# Sensor_Arduino.net
KiCad netlist of a schematic drawn in EAGLE
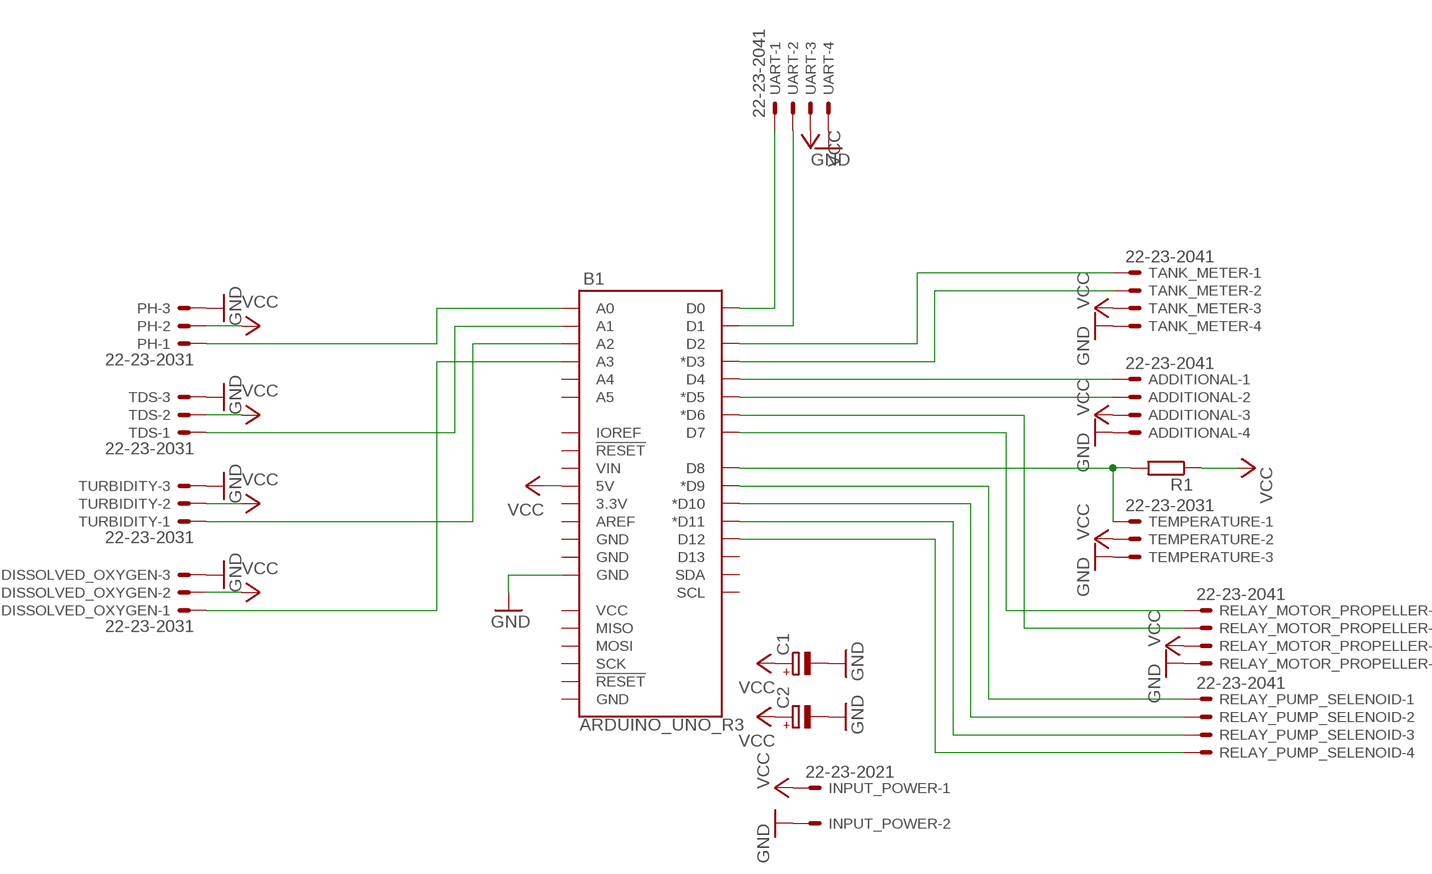
[diagram p0: schematic, sheet 1]

(export (version "E")
  (design (tool "Eeschema 10.0.6"))
  (components
    (comp (ref "ADDITIONAL")
      (value "22-23-2041")
      (footprint "eagle-import:22-23-2041")
      (fields (field (name "MF") "MOLEX"))
      (libsource (lib "eagle-import") (part "22-23-2041"))
    )
    (comp (ref "B1")
      (value "ARDUINO_UNO_R3")
      (footprint "eagle-import:ARDUINO_R3")
      (libsource (lib "eagle-import") (part "ARDUINO_UNO_R3"))
    )
    (comp (ref "C1")
      (value "CPOL-EUE5-10.5")
      (footprint "eagle-import:E5-10,5")
      (libsource (lib "eagle-import") (part "CPOL-EUE5-10.5"))
    )
    (comp (ref "C2")
      (value "CPOL-EUE5-6")
      (footprint "eagle-import:E5-6")
      (libsource (lib "eagle-import") (part "CPOL-EUE5-6"))
    )
    (comp (ref "DISSOLVED_OXYGEN")
      (value "22-23-2031")
      (footprint "eagle-import:22-23-2031")
      (fields (field (name "MF") "MOLEX"))
      (libsource (lib "eagle-import") (part "22-23-2031"))
    )
    (comp (ref "INPUT_POWER")
      (value "22-23-2021")
      (footprint "eagle-import:22-23-2021")
      (fields (field (name "MF") "MOLEX"))
      (libsource (lib "eagle-import") (part "22-23-2021"))
    )
    (comp (ref "PH")
      (value "22-23-2031")
      (footprint "eagle-import:22-23-2031")
      (fields (field (name "MF") "MOLEX"))
      (libsource (lib "eagle-import") (part "22-23-2031"))
    )
    (comp (ref "R1")
      (value "R-EU_0207/12")
      (footprint "eagle-import:0207_12")
      (libsource (lib "eagle-import") (part "R-EU_0207/12"))
    )
    (comp (ref "RELAY_MOTOR_PROPELLER")
      (value "22-23-2041")
      (footprint "eagle-import:22-23-2041")
      (fields (field (name "MF") "MOLEX"))
      (libsource (lib "eagle-import") (part "22-23-2041"))
    )
    (comp (ref "RELAY_PUMP_SELENOID")
      (value "22-23-2041")
      (footprint "eagle-import:22-23-2041")
      (fields (field (name "MF") "MOLEX"))
      (libsource (lib "eagle-import") (part "22-23-2041"))
    )
    (comp (ref "TANK_METER")
      (value "22-23-2041")
      (footprint "eagle-import:22-23-2041")
      (fields (field (name "MF") "MOLEX"))
      (libsource (lib "eagle-import") (part "22-23-2041"))
    )
    (comp (ref "TDS")
      (value "22-23-2031")
      (footprint "eagle-import:22-23-2031")
      (fields (field (name "MF") "MOLEX"))
      (libsource (lib "eagle-import") (part "22-23-2031"))
    )
    (comp (ref "TEMPERATURE")
      (value "22-23-2031")
      (footprint "eagle-import:22-23-2031")
      (fields (field (name "MF") "MOLEX"))
      (libsource (lib "eagle-import") (part "22-23-2031"))
    )
    (comp (ref "TURBIDITY")
      (value "22-23-2031")
      (footprint "eagle-import:22-23-2031")
      (fields (field (name "MF") "MOLEX"))
      (libsource (lib "eagle-import") (part "22-23-2031"))
    )
    (comp (ref "UART")
      (value "22-23-2041")
      (footprint "eagle-import:22-23-2041")
      (fields (field (name "MF") "MOLEX"))
      (libsource (lib "eagle-import") (part "22-23-2041"))
    )
  )
  (nets
    (net (code "1") (name "GND") (class "Default")
      (node (ref "ADDITIONAL") (pin "4") (pinfunction "S_4") (pintype "passive"))
      (node (ref "B1") (pin "GND@2") (pinfunction "GND_GND@2") (pintype "bidirectional"))
      (node (ref "C1") (pin "-") (pinfunction "-_-") (pintype "passive"))
      (node (ref "C2") (pin "-") (pinfunction "-_-") (pintype "passive"))
      (node (ref "DISSOLVED_OXYGEN") (pin "3") (pinfunction "S_3") (pintype "passive"))
      (node (ref "INPUT_POWER") (pin "2") (pinfunction "S_2") (pintype "passive"))
      (node (ref "PH") (pin "3") (pinfunction "S_3") (pintype "passive"))
      (node (ref "RELAY_MOTOR_PROPELLER") (pin "4") (pinfunction "S_4") (pintype "passive"))
      (node (ref "TANK_METER") (pin "4") (pinfunction "S_4") (pintype "passive"))
      (node (ref "TDS") (pin "3") (pinfunction "S_3") (pintype "passive"))
      (node (ref "TEMPERATURE") (pin "3") (pinfunction "S_3") (pintype "passive"))
      (node (ref "TURBIDITY") (pin "3") (pinfunction "S_3") (pintype "passive"))
      (node (ref "UART") (pin "4") (pinfunction "S_4") (pintype "passive"))
    )
    (net (code "2") (name "Net-(ADDITIONALA-S)") (class "Default")
      (node (ref "ADDITIONAL") (pin "1") (pinfunction "S_1") (pintype "passive"))
      (node (ref "B1") (pin "D4") (pinfunction "D4_D4") (pintype "bidirectional"))
    )
    (net (code "3") (name "Net-(ADDITIONALB-S)") (class "Default")
      (node (ref "ADDITIONAL") (pin "2") (pinfunction "S_2") (pintype "passive"))
      (node (ref "B1") (pin "D5") (pinfunction "*D5_D5") (pintype "bidirectional"))
    )
    (net (code "4") (name "Net-(B1-*D3)") (class "Default")
      (node (ref "B1") (pin "D3") (pinfunction "*D3_D3") (pintype "bidirectional"))
      (node (ref "TANK_METER") (pin "2") (pinfunction "S_2") (pintype "passive"))
    )
    (net (code "5") (name "Net-(B1-*D6)") (class "Default")
      (node (ref "B1") (pin "D6") (pinfunction "*D6_D6") (pintype "bidirectional"))
      (node (ref "RELAY_MOTOR_PROPELLER") (pin "2") (pinfunction "S_2") (pintype "passive"))
    )
    (net (code "6") (name "Net-(B1-*D9)") (class "Default")
      (node (ref "B1") (pin "D9") (pinfunction "*D9_D9") (pintype "bidirectional"))
      (node (ref "RELAY_PUMP_SELENOID") (pin "1") (pinfunction "S_1") (pintype "passive"))
    )
    (net (code "7") (name "Net-(B1-*D10)") (class "Default")
      (node (ref "B1") (pin "D10") (pinfunction "*D10_D10") (pintype "bidirectional"))
      (node (ref "RELAY_PUMP_SELENOID") (pin "2") (pinfunction "S_2") (pintype "passive"))
    )
    (net (code "8") (name "Net-(B1-*D11)") (class "Default")
      (node (ref "B1") (pin "D11") (pinfunction "*D11_D11") (pintype "bidirectional"))
      (node (ref "RELAY_PUMP_SELENOID") (pin "3") (pinfunction "S_3") (pintype "passive"))
    )
    (net (code "9") (name "Net-(DISSOLVED_OXYGENA-S)") (class "Default")
      (node (ref "B1") (pin "A3") (pinfunction "A3_A3") (pintype "bidirectional"))
      (node (ref "DISSOLVED_OXYGEN") (pin "1") (pinfunction "S_1") (pintype "passive"))
    )
    (net (code "10") (name "Net-(PHA-S)") (class "Default")
      (node (ref "B1") (pin "A0") (pinfunction "A0_A0") (pintype "bidirectional"))
      (node (ref "PH") (pin "1") (pinfunction "S_1") (pintype "passive"))
    )
    (net (code "11") (name "Net-(RELAY_MOTOR_PROPELLERA-S)") (class "Default")
      (node (ref "B1") (pin "D7") (pinfunction "D7_D7") (pintype "bidirectional"))
      (node (ref "RELAY_MOTOR_PROPELLER") (pin "1") (pinfunction "S_1") (pintype "passive"))
    )
    (net (code "12") (name "Net-(RELAY_PUMP_SELENOIDD-S)") (class "Default")
      (node (ref "B1") (pin "D12") (pinfunction "D12_D12") (pintype "bidirectional"))
      (node (ref "RELAY_PUMP_SELENOID") (pin "4") (pinfunction "S_4") (pintype "passive"))
    )
    (net (code "13") (name "Net-(TANK_METERA-S)") (class "Default")
      (node (ref "B1") (pin "D2") (pinfunction "D2_D2") (pintype "bidirectional"))
      (node (ref "TANK_METER") (pin "1") (pinfunction "S_1") (pintype "passive"))
    )
    (net (code "14") (name "Net-(TDSA-S)") (class "Default")
      (node (ref "B1") (pin "A1") (pinfunction "A1_A1") (pintype "bidirectional"))
      (node (ref "TDS") (pin "1") (pinfunction "S_1") (pintype "passive"))
    )
    (net (code "15") (name "Net-(TEMPERATUREA-S)") (class "Default")
      (node (ref "B1") (pin "D8") (pinfunction "D8_D8") (pintype "bidirectional"))
      (node (ref "R1") (pin "2") (pinfunction "2_2") (pintype "passive"))
      (node (ref "TEMPERATURE") (pin "1") (pinfunction "S_1") (pintype "passive"))
    )
    (net (code "16") (name "Net-(TURBIDITYA-S)") (class "Default")
      (node (ref "B1") (pin "A2") (pinfunction "A2_A2") (pintype "bidirectional"))
      (node (ref "TURBIDITY") (pin "1") (pinfunction "S_1") (pintype "passive"))
    )
    (net (code "17") (name "Net-(UARTA-S)") (class "Default")
      (node (ref "B1") (pin "D0") (pinfunction "D0_D0") (pintype "bidirectional"))
      (node (ref "UART") (pin "1") (pinfunction "S_1") (pintype "passive"))
    )
    (net (code "18") (name "Net-(UARTB-S)") (class "Default")
      (node (ref "B1") (pin "D1") (pinfunction "D1_D1") (pintype "bidirectional"))
      (node (ref "UART") (pin "2") (pinfunction "S_2") (pintype "passive"))
    )
    (net (code "19") (name "VCC") (class "Default")
      (node (ref "ADDITIONAL") (pin "3") (pinfunction "S_3") (pintype "passive"))
      (node (ref "B1") (pin "5V") (pinfunction "5V_5V") (pintype "bidirectional"))
      (node (ref "C1") (pin "+") (pinfunction "+_+") (pintype "passive"))
      (node (ref "C2") (pin "+") (pinfunction "+_+") (pintype "passive"))
      (node (ref "DISSOLVED_OXYGEN") (pin "2") (pinfunction "S_2") (pintype "passive"))
      (node (ref "INPUT_POWER") (pin "1") (pinfunction "S_1") (pintype "passive"))
      (node (ref "PH") (pin "2") (pinfunction "S_2") (pintype "passive"))
      (node (ref "R1") (pin "1") (pinfunction "1_1") (pintype "passive"))
      (node (ref "RELAY_MOTOR_PROPELLER") (pin "3") (pinfunction "S_3") (pintype "passive"))
      (node (ref "TANK_METER") (pin "3") (pinfunction "S_3") (pintype "passive"))
      (node (ref "TDS") (pin "2") (pinfunction "S_2") (pintype "passive"))
      (node (ref "TEMPERATURE") (pin "2") (pinfunction "S_2") (pintype "passive"))
      (node (ref "TURBIDITY") (pin "2") (pinfunction "S_2") (pintype "passive"))
      (node (ref "UART") (pin "3") (pinfunction "S_3") (pintype "passive"))
    )
    (net (code "20") (name "unconnected-(B1-GND-PadGND@1)") (class "Default")
      (node (ref "B1") (pin "GND@1") (pinfunction "GND_GND@1") (pintype "bidirectional"))
    )
    (net (code "21") (name "unconnected-(B1-GND-PadGND@3)") (class "Default")
      (node (ref "B1") (pin "GND@3") (pinfunction "GND_GND@3") (pintype "bidirectional"))
    )
    (net (code "22") (name "unconnected-(B1-GND-PadGND@4)") (class "Default")
      (node (ref "B1") (pin "GND@4") (pinfunction "GND_GND@4") (pintype "bidirectional"))
    )
    (net (code "23") (name "unconnected-(B1-Pad3.3V)") (class "Default")
      (node (ref "B1") (pin "3.3V") (pinfunction "3.3V_3.3V") (pintype "bidirectional"))
    )
    (net (code "24") (name "unconnected-(B1-PadA4)") (class "Default")
      (node (ref "B1") (pin "A4") (pinfunction "A4_A4") (pintype "bidirectional"))
    )
    (net (code "25") (name "unconnected-(B1-PadA5)") (class "Default")
      (node (ref "B1") (pin "A5") (pinfunction "A5_A5") (pintype "bidirectional"))
    )
    (net (code "26") (name "unconnected-(B1-PadAREF)") (class "Default")
      (node (ref "B1") (pin "AREF") (pinfunction "AREF_AREF") (pintype "bidirectional"))
    )
    (net (code "27") (name "unconnected-(B1-PadD13)") (class "Default")
      (node (ref "B1") (pin "D13") (pinfunction "D13_D13") (pintype "bidirectional"))
    )
    (net (code "28") (name "unconnected-(B1-PadIOREF)") (class "Default")
      (node (ref "B1") (pin "IOREF") (pinfunction "IOREF_IOREF") (pintype "bidirectional"))
    )
    (net (code "29") (name "unconnected-(B1-PadMISO)") (class "Default")
      (node (ref "B1") (pin "MISO") (pinfunction "MISO_MISO") (pintype "bidirectional"))
    )
    (net (code "30") (name "unconnected-(B1-PadMOSI)") (class "Default")
      (node (ref "B1") (pin "MOSI") (pinfunction "MOSI_MOSI") (pintype "bidirectional"))
    )
    (net (code "31") (name "unconnected-(B1-PadSCK)") (class "Default")
      (node (ref "B1") (pin "SCK") (pinfunction "SCK_SCK") (pintype "bidirectional"))
    )
    (net (code "32") (name "unconnected-(B1-PadSCL)") (class "Default")
      (node (ref "B1") (pin "SCL") (pinfunction "SCL_SCL") (pintype "bidirectional"))
    )
    (net (code "33") (name "unconnected-(B1-PadSDA)") (class "Default")
      (node (ref "B1") (pin "SDA") (pinfunction "SDA_SDA") (pintype "bidirectional"))
    )
    (net (code "34") (name "unconnected-(B1-PadVCC)") (class "Default")
      (node (ref "B1") (pin "VCC") (pinfunction "VCC_VCC") (pintype "bidirectional"))
    )
    (net (code "35") (name "unconnected-(B1-PadVIN)") (class "Default")
      (node (ref "B1") (pin "VIN") (pinfunction "VIN_VIN") (pintype "bidirectional"))
    )
    (net (code "36") (name "unconnected-(B1-~{RESET}-PadRESET@1)") (class "Default")
      (node (ref "B1") (pin "RESET@1") (pinfunction "~{RESET}_RESET@1") (pintype "bidirectional"))
    )
    (net (code "37") (name "unconnected-(B1-~{RESET}-PadRESET@2)") (class "Default")
      (node (ref "B1") (pin "RESET@2") (pinfunction "~{RESET}_RESET@2") (pintype "bidirectional"))
    )
  )
)
